# zb_sensor.net
KiCad netlist of a schematic drawn in Altium Designer
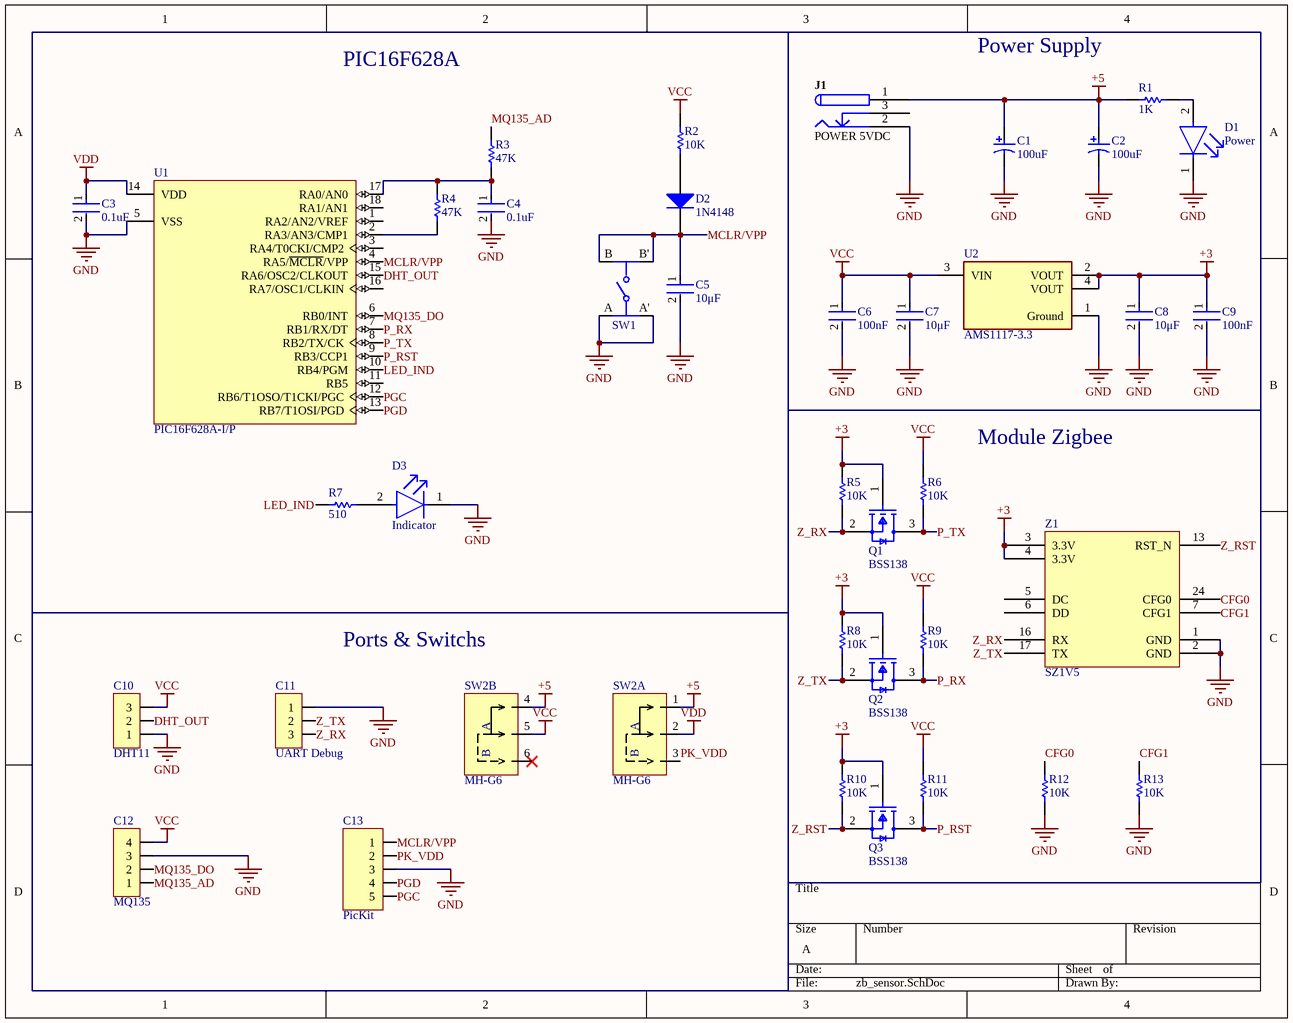
[diagram p0: zb_sensor.SchDoc]

(export (version "E")
  (design (tool "Eeschema 10.0.6"))
  (components
    (comp (ref "C1")
      (value "100uF")
      (footprint "PNSC-FK-V-D8_V")
      (fields (field (name "MANUFACTURER") "Panasonic"))
      (libsource (lib "Altium Content Vault") (part "CAP-P-2"))
    )
    (comp (ref "C2")
      (value "100uF")
      (footprint "PNSC-FK-V-D8_V")
      (fields (field (name "MANUFACTURER") "Panasonic"))
      (libsource (lib "Altium Content Vault") (part "CAP-P-2"))
    )
    (comp (ref "C3")
      (value "0.1uF")
      (footprint "FP-0603-L_1_6_0_15-W_0_81-IPC_A")
      (description "General Purpose Ceramic Capacitor, 0603, 100nF, 10%, X7R, 15%, 50V")
      (fields (field (name "TOLERANCE") "10%") (field (name "VOLTAGE") "50V"))
      (libsource (lib "Altium Content Vault") (part "02cd4be3c70576c341d710602a673aa"))
    )
    (comp (ref "C4")
      (value "0.1uF")
      (footprint "FP-0603-L_1_6_0_15-W_0_81-IPC_A")
      (description "General Purpose Ceramic Capacitor, 0603, 100nF, 10%, X7R, 15%, 50V")
      (fields (field (name "TOLERANCE") "10%") (field (name "VOLTAGE") "50V"))
      (libsource (lib "Altium Content Vault") (part "02cd4be3c70576c341d710602a673aa"))
    )
    (comp (ref "C5")
      (value "10μF")
      (footprint "FP-0603-L_1_6_0_15-W_0_81-IPC_A")
      (description "General Purpose Ceramic Capacitor, 0603, 100nF, 10%, X7R, 15%, 50V")
      (fields (field (name "TOLERANCE") "10%") (field (name "VOLTAGE") "50V"))
      (libsource (lib "Altium Content Vault") (part "02cd4be3c70576c341d710602a673aa"))
    )
    (comp (ref "C6")
      (value "100nF")
      (footprint "FP-0603-L_1_6_0_15-W_0_81-IPC_A")
      (description "General Purpose Ceramic Capacitor, 0603, 100nF, 10%, X7R, 15%, 50V")
      (fields (field (name "TOLERANCE") "10%") (field (name "VOLTAGE") "50V"))
      (libsource (lib "Altium Content Vault") (part "02cd4be3c70576c341d710602a673aa"))
    )
    (comp (ref "C7")
      (value "10μF")
      (footprint "FP-0603-L_1_6_0_15-W_0_81-IPC_A")
      (description "General Purpose Ceramic Capacitor, 0603, 100nF, 10%, X7R, 15%, 50V")
      (fields (field (name "TOLERANCE") "10%") (field (name "VOLTAGE") "50V"))
      (libsource (lib "Altium Content Vault") (part "02cd4be3c70576c341d710602a673aa"))
    )
    (comp (ref "C8")
      (value "10μF")
      (footprint "FP-0603-L_1_6_0_15-W_0_81-IPC_A")
      (description "General Purpose Ceramic Capacitor, 0603, 100nF, 10%, X7R, 15%, 50V")
      (fields (field (name "TOLERANCE") "10%") (field (name "VOLTAGE") "50V"))
      (libsource (lib "Altium Content Vault") (part "02cd4be3c70576c341d710602a673aa"))
    )
    (comp (ref "C9")
      (value "100nF")
      (footprint "FP-0603-L_1_6_0_15-W_0_81-IPC_A")
      (description "General Purpose Ceramic Capacitor, 0603, 100nF, 10%, X7R, 15%, 50V")
      (fields (field (name "TOLERANCE") "10%") (field (name "VOLTAGE") "50V"))
      (libsource (lib "Altium Content Vault") (part "02cd4be3c70576c341d710602a673aa"))
    )
    (comp (ref "C10")
      (value "DHT11")
      (footprint "JP3-D1C")
      (description "WR-PHD 2.54 mm Angled Socket Header")
      (fields
        (field (name "MANUFACTURER") "Würth Elektronik eiSos GmbH")
        (field (name "PARTNO") "613003143121")
        (field (name "CREATED BY") "Karrer Zheng")
      )
      (libsource (lib "TechMT.VN_Lib_Project v2") (part "JP3"))
    )
    (comp (ref "C11")
      (value "UART Debug")
      (footprint "JP3-D1C")
      (description "WR-PHD 2.54 mm Angled Socket Header")
      (fields
        (field (name "MANUFACTURER") "Würth Elektronik eiSos GmbH")
        (field (name "PARTNO") "613003143121")
        (field (name "CREATED BY") "Karrer Zheng")
      )
      (libsource (lib "") (part "JP3_1"))
    )
    (comp (ref "C12")
      (value "MQ135")
      (footprint "JP4-D1C")
      (description "WR-PHD 2.54 mm Angled Socket Header")
      (fields
        (field (name "MANUFACTURER") "Würth Elektronik eiSos GmbH")
        (field (name "PARTNO") "613004143121")
        (field (name "CREATED BY") "Karrer Zheng")
      )
      (libsource (lib "TechMT.VN_Lib_Project v2") (part "JP4"))
    )
    (comp (ref "C13")
      (value "PicKit")
      (footprint "JP5-D1C")
      (description "WR-PHD 2.54 mm Angled Socket Header")
      (fields
        (field (name "MANUFACTURER") "Würth Elektronik eiSos GmbH")
        (field (name "PARTNO") "613005143121")
        (field (name "CREATED BY") "Karrer Zheng")
      )
      (libsource (lib "TechMT.VN_Lib_Project v2") (part "JP5"))
    )
    (comp (ref "D1")
      (value "Power")
      (footprint "FP-HLMP-4700-MFG")
      (description "LED RED DIFFUSED T-1 3/4 T/H")
      (fields
        (field (name "OCTOPART") "https://octopart.com/hlmp-4700-broadcom-71130526")
        (field (name "MANUFACTURER") "Broadcom")
      )
      (libsource (lib "Altium Content Vault") (part "8706943c75ba83719d021d2fdc84c58"))
    )
    (comp (ref "D2")
      (value "1N4148")
      (footprint "NXP-SOD27-2_V")
      (description "High-speed Diode, 100 V, 450 mA, 2-Pin SOD27, RoHS")
      (fields (field (name "MANUFACTURER") "NXP Semiconductors"))
      (libsource (lib "Altium Content Vault") (part "NXP-A1K2-2"))
    )
    (comp (ref "D3")
      (value "Indicator")
      (footprint "FP-HLMP-4700-MFG")
      (description "LED RED DIFFUSED T-1 3/4 T/H")
      (fields
        (field (name "OCTOPART") "https://octopart.com/hlmp-4700-broadcom-71130526")
        (field (name "MANUFACTURER") "Broadcom")
      )
      (libsource (lib "Altium Content Vault") (part "8706943c75ba83719d021d2fdc84c58"))
    )
    (comp (ref "J1")
      (value "POWER 5VDC")
      (footprint "KYCN-KLDX-0202-B_V")
      (description "3 Conductor Power Jack, 2 break 2 aux contacts")
      (fields (field (name "PARTNUMBER") "KLDX-0202-B"))
      (libsource (lib "Altium Content Vault") (part "KYCN-KLDX-0202-B-3"))
    )
    (comp (ref "Q1")
      (value "BSS138")
      (footprint "FP-318-08-IPC_B")
      (description "MOSFET N-CH 50V 220MA SOT-23")
      (libsource (lib "Altium Content Vault") (part "3b9c635fedb024a5347a57b145af9cc"))
    )
    (comp (ref "Q2")
      (value "BSS138")
      (footprint "FP-318-08-IPC_B")
      (description "MOSFET N-CH 50V 220MA SOT-23")
      (libsource (lib "Altium Content Vault") (part "3b9c635fedb024a5347a57b145af9cc"))
    )
    (comp (ref "Q3")
      (value "BSS138")
      (footprint "FP-318-08-IPC_B")
      (description "MOSFET N-CH 50V 220MA SOT-23")
      (libsource (lib "Altium Content Vault") (part "3b9c635fedb024a5347a57b145af9cc"))
    )
    (comp (ref "R1")
      (value "1K")
      (footprint "RESC1609X55X30ML15T15")
      (description "Chip Resistor, 10 KOhm, +/- 1%, 0.1 W, -55 to 155 degC, 0603 (1608 Metric), RoHS, Tape and Reel")
      (fields (field (name "TOLERANCE") "1%") (field (name "MANUFACTURER") "Panasonic"))
      (libsource (lib "Altium Content Vault") (part "RES-2"))
    )
    (comp (ref "R2")
      (value "10K")
      (footprint "RESC1609X55X30ML15T15")
      (description "Chip Resistor, 10 KOhm, +/- 1%, 0.1 W, -55 to 155 degC, 0603 (1608 Metric), RoHS, Tape and Reel")
      (fields (field (name "TOLERANCE") "1%") (field (name "MANUFACTURER") "Panasonic"))
      (libsource (lib "Altium Content Vault") (part "RES-2"))
    )
    (comp (ref "R3")
      (value "47K")
      (footprint "RESC1609X55X30ML15T15")
      (description "Chip Resistor, 10 KOhm, +/- 1%, 0.1 W, -55 to 155 degC, 0603 (1608 Metric), RoHS, Tape and Reel")
      (fields (field (name "TOLERANCE") "1%") (field (name "MANUFACTURER") "Panasonic"))
      (libsource (lib "Altium Content Vault") (part "RES-2"))
    )
    (comp (ref "R4")
      (value "47K")
      (footprint "RESC1609X55X30ML15T15")
      (description "Chip Resistor, 10 KOhm, +/- 1%, 0.1 W, -55 to 155 degC, 0603 (1608 Metric), RoHS, Tape and Reel")
      (fields (field (name "TOLERANCE") "1%") (field (name "MANUFACTURER") "Panasonic"))
      (libsource (lib "Altium Content Vault") (part "RES-2"))
    )
    (comp (ref "R5")
      (value "10K")
      (footprint "RESC1609X55X30ML15T15")
      (description "Chip Resistor, 10 KOhm, +/- 1%, 0.1 W, -55 to 155 degC, 0603 (1608 Metric), RoHS, Tape and Reel")
      (fields (field (name "TOLERANCE") "1%") (field (name "MANUFACTURER") "Panasonic"))
      (libsource (lib "Altium Content Vault") (part "RES-2"))
    )
    (comp (ref "R6")
      (value "10K")
      (footprint "RESC1609X55X30ML15T15")
      (description "Chip Resistor, 10 KOhm, +/- 1%, 0.1 W, -55 to 155 degC, 0603 (1608 Metric), RoHS, Tape and Reel")
      (fields (field (name "TOLERANCE") "1%") (field (name "MANUFACTURER") "Panasonic"))
      (libsource (lib "Altium Content Vault") (part "RES-2"))
    )
    (comp (ref "R7")
      (value "510")
      (footprint "RESC1609X55X30ML15T15")
      (description "Chip Resistor, 10 KOhm, +/- 1%, 0.1 W, -55 to 155 degC, 0603 (1608 Metric), RoHS, Tape and Reel")
      (fields (field (name "TOLERANCE") "1%") (field (name "MANUFACTURER") "Panasonic"))
      (libsource (lib "Altium Content Vault") (part "RES-2"))
    )
    (comp (ref "R8")
      (value "10K")
      (footprint "RESC1609X55X30ML15T15")
      (description "Chip Resistor, 10 KOhm, +/- 1%, 0.1 W, -55 to 155 degC, 0603 (1608 Metric), RoHS, Tape and Reel")
      (fields (field (name "TOLERANCE") "1%") (field (name "MANUFACTURER") "Panasonic"))
      (libsource (lib "Altium Content Vault") (part "RES-2"))
    )
    (comp (ref "R9")
      (value "10K")
      (footprint "RESC1609X55X30ML15T15")
      (description "Chip Resistor, 10 KOhm, +/- 1%, 0.1 W, -55 to 155 degC, 0603 (1608 Metric), RoHS, Tape and Reel")
      (fields (field (name "TOLERANCE") "1%") (field (name "MANUFACTURER") "Panasonic"))
      (libsource (lib "Altium Content Vault") (part "RES-2"))
    )
    (comp (ref "R10")
      (value "10K")
      (footprint "RESC1609X55X30ML15T15")
      (description "Chip Resistor, 10 KOhm, +/- 1%, 0.1 W, -55 to 155 degC, 0603 (1608 Metric), RoHS, Tape and Reel")
      (fields (field (name "TOLERANCE") "1%") (field (name "MANUFACTURER") "Panasonic"))
      (libsource (lib "Altium Content Vault") (part "RES-2"))
    )
    (comp (ref "R11")
      (value "10K")
      (footprint "RESC1609X55X30ML15T15")
      (description "Chip Resistor, 10 KOhm, +/- 1%, 0.1 W, -55 to 155 degC, 0603 (1608 Metric), RoHS, Tape and Reel")
      (fields (field (name "TOLERANCE") "1%") (field (name "MANUFACTURER") "Panasonic"))
      (libsource (lib "Altium Content Vault") (part "RES-2"))
    )
    (comp (ref "R12")
      (value "10K")
      (footprint "RESC1609X55X30ML15T15")
      (description "Chip Resistor, 10 KOhm, +/- 1%, 0.1 W, -55 to 155 degC, 0603 (1608 Metric), RoHS, Tape and Reel")
      (fields (field (name "TOLERANCE") "1%") (field (name "MANUFACTURER") "Panasonic"))
      (libsource (lib "Altium Content Vault") (part "RES-2"))
    )
    (comp (ref "R13")
      (value "10K")
      (footprint "RESC1609X55X30ML15T15")
      (description "Chip Resistor, 10 KOhm, +/- 1%, 0.1 W, -55 to 155 degC, 0603 (1608 Metric), RoHS, Tape and Reel")
      (fields (field (name "TOLERANCE") "1%") (field (name "MANUFACTURER") "Panasonic"))
      (libsource (lib "Altium Content Vault") (part "RES-2"))
    )
    (comp (ref "SW1")
      (value "RESET")
      (footprint "FP-EVQ-PAG05R-MFG")
      (description "SWITCH TACTILE SPST-NO 0.02A 15V")
      (libsource (lib "Altium Content Vault") (part "841f23923f71b23f3ea0ab5dfb78dcc"))
    )
    (comp (ref "SW2")
      (value "MH-G6")
      (footprint "MH-G6")
      (description "6-pin switch MH-G6 2.54mm")
      (libsource (lib "MH-G6") (part "MH-G6"))
    )
    (comp (ref "U1")
      (value "PIC16F628A-I/P")
      (footprint "PDIP300-P18")
      (libsource (lib "Altium Content Vault") (part "MC-8B-16F627A-IL18"))
    )
    (comp (ref "U2")
      (value "AMS1117-3.3")
      (footprint "FP-AMS1117-IPC_A")
      (description "LDO Voltage Regulators 1A, 3.3V")
      (fields
        (field (name "OCTOPART") "https://octopart.com/ams1117-3.3-advanced+monolithic+systems-25899300")
        (field (name "MANUFACTURER") "Advanced Monolithic Systems")
      )
      (libsource (lib "Altium Content Vault") (part "8bdbb5f8e77002000e30dd2845d0354"))
    )
    (comp (ref "Z1")
      (value "SZ1V5")
      (footprint "SZ1V5 PINOUT MODULE")
      (libsource (lib "SZ1V5") (part "SZ1V5_Alt"))
    )
  )
  (nets
    (net (code "1") (name "+3") (class "Default")
      (node (ref "C8") (pin "1") (pinfunction "1_1") (pintype "passive"))
      (node (ref "C9") (pin "1") (pinfunction "1_1") (pintype "passive"))
      (node (ref "Q1") (pin "1") (pinfunction "G_1") (pintype "passive"))
      (node (ref "Q2") (pin "1") (pinfunction "G_1") (pintype "passive"))
      (node (ref "Q3") (pin "1") (pinfunction "G_1") (pintype "passive"))
      (node (ref "R10") (pin "2") (pinfunction "2_2") (pintype "passive"))
      (node (ref "R5") (pin "2") (pinfunction "2_2") (pintype "passive"))
      (node (ref "R8") (pin "2") (pinfunction "2_2") (pintype "passive"))
      (node (ref "U2") (pin "2") (pinfunction "VOUT_2") (pintype "passive"))
      (node (ref "U2") (pin "4") (pinfunction "VOUT_4") (pintype "passive"))
      (node (ref "Z1") (pin "3") (pinfunction "3.3V_3") (pintype "passive"))
      (node (ref "Z1") (pin "4") (pinfunction "3.3V_4") (pintype "passive"))
    )
    (net (code "2") (name "+5") (class "Default")
      (node (ref "C1") (pin "1") (pinfunction "1_1") (pintype "passive"))
      (node (ref "C2") (pin "1") (pinfunction "1_1") (pintype "passive"))
      (node (ref "J1") (pin "1") (pintype "power_in"))
      (node (ref "R1") (pin "2") (pinfunction "2_2") (pintype "passive"))
      (node (ref "SW2") (pin "1") (pinfunction "A_1") (pintype "passive"))
      (node (ref "SW2") (pin "4") (pinfunction "A_4") (pintype "passive"))
    )
    (net (code "3") (name "/CFG0") (class "Default")
      (node (ref "R12") (pin "2") (pinfunction "2_2") (pintype "passive"))
      (node (ref "Z1") (pin "24") (pinfunction "CFG0_24") (pintype "passive"))
    )
    (net (code "4") (name "/CFG1") (class "Default")
      (node (ref "R13") (pin "2") (pinfunction "2_2") (pintype "passive"))
      (node (ref "Z1") (pin "7") (pinfunction "CFG1_7") (pintype "passive"))
    )
    (net (code "5") (name "/DHT_OUT") (class "Default")
      (node (ref "C10") (pin "2") (pinfunction "2_2") (pintype "passive"))
      (node (ref "U1") (pin "15") (pinfunction "RA6/OSC2/CLKOUT_15") (pintype "bidirectional"))
    )
    (net (code "6") (name "/LED_IND") (class "Default")
      (node (ref "R7") (pin "2") (pinfunction "2_2") (pintype "passive"))
      (node (ref "U1") (pin "10") (pinfunction "RB4/PGM_10") (pintype "bidirectional"))
    )
    (net (code "7") (name "/MCLR{slash}VPP") (class "Default")
      (node (ref "C13") (pin "1") (pinfunction "1_1") (pintype "passive"))
      (node (ref "C5") (pin "1") (pinfunction "1_1") (pintype "passive"))
      (node (ref "D2") (pin "2") (pinfunction "K_2") (pintype "passive"))
      (node (ref "SW1") (pin "B") (pinfunction "B_B") (pintype "passive"))
      (node (ref "SW1") (pin "B'") (pinfunction "B'_B'") (pintype "passive"))
      (node (ref "U1") (pin "4") (pinfunction "RA5/~{MCLR}/VPP_4") (pintype "bidirectional"))
    )
    (net (code "8") (name "/MQ135_AD") (class "Default")
      (node (ref "C12") (pin "1") (pinfunction "1_1") (pintype "passive"))
      (node (ref "R3") (pin "2") (pinfunction "2_2") (pintype "passive"))
    )
    (net (code "9") (name "/MQ135_DO") (class "Default")
      (node (ref "C12") (pin "2") (pinfunction "2_2") (pintype "passive"))
      (node (ref "U1") (pin "6") (pinfunction "RB0/INT_6") (pintype "bidirectional"))
    )
    (net (code "10") (name "/PGC") (class "Default")
      (node (ref "C13") (pin "5") (pinfunction "5_5") (pintype "passive"))
      (node (ref "U1") (pin "12") (pinfunction "RB6/T1OSO/T1CKI/PGC_12") (pintype "bidirectional"))
    )
    (net (code "11") (name "/PGD") (class "Default")
      (node (ref "C13") (pin "4") (pinfunction "4_4") (pintype "passive"))
      (node (ref "U1") (pin "13") (pinfunction "RB7/T1OSI/PGD_13") (pintype "bidirectional"))
    )
    (net (code "12") (name "/PK_VDD") (class "Default")
      (node (ref "C13") (pin "2") (pinfunction "2_2") (pintype "passive"))
      (node (ref "SW2") (pin "3") (pinfunction "B_3") (pintype "passive"))
    )
    (net (code "13") (name "/P_RST") (class "Default")
      (node (ref "Q3") (pin "3") (pinfunction "D_3") (pintype "passive"))
      (node (ref "R11") (pin "1") (pinfunction "1_1") (pintype "passive"))
      (node (ref "U1") (pin "9") (pinfunction "RB3/CCP1_9") (pintype "bidirectional"))
    )
    (net (code "14") (name "/P_RX") (class "Default")
      (node (ref "Q2") (pin "3") (pinfunction "D_3") (pintype "passive"))
      (node (ref "R9") (pin "1") (pinfunction "1_1") (pintype "passive"))
      (node (ref "U1") (pin "7") (pinfunction "RB1/RX/DT_7") (pintype "bidirectional"))
    )
    (net (code "15") (name "/P_TX") (class "Default")
      (node (ref "Q1") (pin "3") (pinfunction "D_3") (pintype "passive"))
      (node (ref "R6") (pin "1") (pinfunction "1_1") (pintype "passive"))
      (node (ref "U1") (pin "8") (pinfunction "RB2/TX/CK_8") (pintype "bidirectional"))
    )
    (net (code "16") (name "/Z_RST") (class "Default")
      (node (ref "Q3") (pin "2") (pinfunction "S_2") (pintype "passive"))
      (node (ref "R10") (pin "1") (pinfunction "1_1") (pintype "passive"))
      (node (ref "Z1") (pin "13") (pinfunction "RST_N_13") (pintype "passive"))
    )
    (net (code "17") (name "/Z_RX") (class "Default")
      (node (ref "C11") (pin "3") (pinfunction "3_3") (pintype "passive"))
      (node (ref "Q1") (pin "2") (pinfunction "S_2") (pintype "passive"))
      (node (ref "R5") (pin "1") (pinfunction "1_1") (pintype "passive"))
      (node (ref "Z1") (pin "16") (pinfunction "RX_16") (pintype "passive"))
    )
    (net (code "18") (name "/Z_TX") (class "Default")
      (node (ref "C11") (pin "2") (pinfunction "2_2") (pintype "passive"))
      (node (ref "Q2") (pin "2") (pinfunction "S_2") (pintype "passive"))
      (node (ref "R8") (pin "1") (pinfunction "1_1") (pintype "passive"))
      (node (ref "Z1") (pin "17") (pinfunction "TX_17") (pintype "passive"))
    )
    (net (code "19") (name "GND") (class "Default")
      (node (ref "C1") (pin "2") (pinfunction "2_2") (pintype "passive"))
      (node (ref "C10") (pin "1") (pinfunction "1_1") (pintype "passive"))
      (node (ref "C11") (pin "1") (pinfunction "1_1") (pintype "passive"))
      (node (ref "C12") (pin "3") (pinfunction "3_3") (pintype "passive"))
      (node (ref "C13") (pin "3") (pinfunction "3_3") (pintype "passive"))
      (node (ref "C2") (pin "2") (pinfunction "2_2") (pintype "passive"))
      (node (ref "C3") (pin "2") (pinfunction "2_2") (pintype "passive"))
      (node (ref "C4") (pin "2") (pinfunction "2_2") (pintype "passive"))
      (node (ref "C5") (pin "2") (pinfunction "2_2") (pintype "passive"))
      (node (ref "C6") (pin "2") (pinfunction "2_2") (pintype "passive"))
      (node (ref "C7") (pin "2") (pinfunction "2_2") (pintype "passive"))
      (node (ref "C8") (pin "2") (pinfunction "2_2") (pintype "passive"))
      (node (ref "C9") (pin "2") (pinfunction "2_2") (pintype "passive"))
      (node (ref "D1") (pin "1") (pinfunction "C_1") (pintype "passive"))
      (node (ref "D3") (pin "1") (pinfunction "C_1") (pintype "passive"))
      (node (ref "J1") (pin "2") (pintype "power_in"))
      (node (ref "R12") (pin "1") (pinfunction "1_1") (pintype "passive"))
      (node (ref "R13") (pin "1") (pinfunction "1_1") (pintype "passive"))
      (node (ref "SW1") (pin "A") (pinfunction "A_A") (pintype "passive"))
      (node (ref "SW1") (pin "A'") (pinfunction "A'_A'") (pintype "passive"))
      (node (ref "U1") (pin "5") (pinfunction "VSS_5") (pintype "power_in"))
      (node (ref "U2") (pin "1") (pinfunction "Ground_1") (pintype "power_in"))
      (node (ref "Z1") (pin "1") (pinfunction "GND_1") (pintype "passive"))
      (node (ref "Z1") (pin "2") (pinfunction "GND_2") (pintype "passive"))
    )
    (net (code "20") (name "Net-(D1-A)") (class "Default")
      (node (ref "D1") (pin "2") (pinfunction "A_2") (pintype "passive"))
      (node (ref "R1") (pin "1") (pinfunction "1_1") (pintype "passive"))
    )
    (net (code "21") (name "Net-(D2-A)") (class "Default")
      (node (ref "D2") (pin "1") (pinfunction "A_1") (pintype "passive"))
      (node (ref "R2") (pin "1") (pinfunction "1_1") (pintype "passive"))
    )
    (net (code "22") (name "Net-(D3-A)") (class "Default")
      (node (ref "D3") (pin "2") (pinfunction "A_2") (pintype "passive"))
      (node (ref "R7") (pin "1") (pinfunction "1_1") (pintype "passive"))
    )
    (net (code "23") (name "Net-(U1-RA0{slash}AN0)") (class "Default")
      (node (ref "C4") (pin "1") (pinfunction "1_1") (pintype "passive"))
      (node (ref "R3") (pin "1") (pinfunction "1_1") (pintype "passive"))
      (node (ref "R4") (pin "2") (pinfunction "2_2") (pintype "passive"))
      (node (ref "U1") (pin "17") (pinfunction "RA0/AN0_17") (pintype "bidirectional"))
    )
    (net (code "24") (name "Net-(U1-RA3{slash}AN3{slash}CMP1)") (class "Default")
      (node (ref "R4") (pin "1") (pinfunction "1_1") (pintype "passive"))
      (node (ref "U1") (pin "2") (pinfunction "RA3/AN3/CMP1_2") (pintype "bidirectional"))
    )
    (net (code "25") (name "VCC") (class "Default")
      (node (ref "C10") (pin "3") (pinfunction "3_3") (pintype "passive"))
      (node (ref "C12") (pin "4") (pinfunction "4_4") (pintype "passive"))
      (node (ref "C6") (pin "1") (pinfunction "1_1") (pintype "passive"))
      (node (ref "C7") (pin "1") (pinfunction "1_1") (pintype "passive"))
      (node (ref "R11") (pin "2") (pinfunction "2_2") (pintype "passive"))
      (node (ref "R2") (pin "2") (pinfunction "2_2") (pintype "passive"))
      (node (ref "R6") (pin "2") (pinfunction "2_2") (pintype "passive"))
      (node (ref "R9") (pin "2") (pinfunction "2_2") (pintype "passive"))
      (node (ref "SW2") (pin "5") (pinfunction "COM_5") (pintype "passive"))
      (node (ref "U2") (pin "3") (pinfunction "VIN_3") (pintype "power_in"))
    )
    (net (code "26") (name "VDD") (class "Default")
      (node (ref "C3") (pin "1") (pinfunction "1_1") (pintype "passive"))
      (node (ref "SW2") (pin "2") (pinfunction "COM_2") (pintype "passive"))
      (node (ref "U1") (pin "14") (pinfunction "VDD_14") (pintype "power_in"))
    )
    (net (code "27") (name "unconnected-(J1-Pad3)") (class "Default")
      (node (ref "J1") (pin "3") (pintype "power_in"))
    )
    (net (code "28") (name "unconnected-(SW2B-B-Pad6)") (class "Default")
      (node (ref "SW2") (pin "6") (pinfunction "B_6") (pintype "passive+no_connect"))
    )
    (net (code "29") (name "unconnected-(U1-RA1{slash}AN1-Pad18)") (class "Default")
      (node (ref "U1") (pin "18") (pinfunction "RA1/AN1_18") (pintype "bidirectional"))
    )
    (net (code "30") (name "unconnected-(U1-RA2{slash}AN2{slash}VREF-Pad1)") (class "Default")
      (node (ref "U1") (pin "1") (pinfunction "RA2/AN2/VREF_1") (pintype "bidirectional"))
    )
    (net (code "31") (name "unconnected-(U1-RA4{slash}T0CKI{slash}CMP2-Pad3)") (class "Default")
      (node (ref "U1") (pin "3") (pinfunction "RA4/T0CKI/CMP2_3") (pintype "bidirectional"))
    )
    (net (code "32") (name "unconnected-(U1-RA7{slash}OSC1{slash}CLKIN-Pad16)") (class "Default")
      (node (ref "U1") (pin "16") (pinfunction "RA7/OSC1/CLKIN_16") (pintype "bidirectional"))
    )
    (net (code "33") (name "unconnected-(U1-RB5-Pad11)") (class "Default")
      (node (ref "U1") (pin "11") (pinfunction "RB5_11") (pintype "bidirectional"))
    )
    (net (code "34") (name "unconnected-(Z1-DC-Pad5)") (class "Default")
      (node (ref "Z1") (pin "5") (pinfunction "DC_5") (pintype "passive"))
    )
    (net (code "35") (name "unconnected-(Z1-DD-Pad6)") (class "Default")
      (node (ref "Z1") (pin "6") (pinfunction "DD_6") (pintype "passive"))
    )
  )
)
